# Dust1_MotherBoard_MCU.net
KiCad netlist of a schematic drawn in Altium Designer
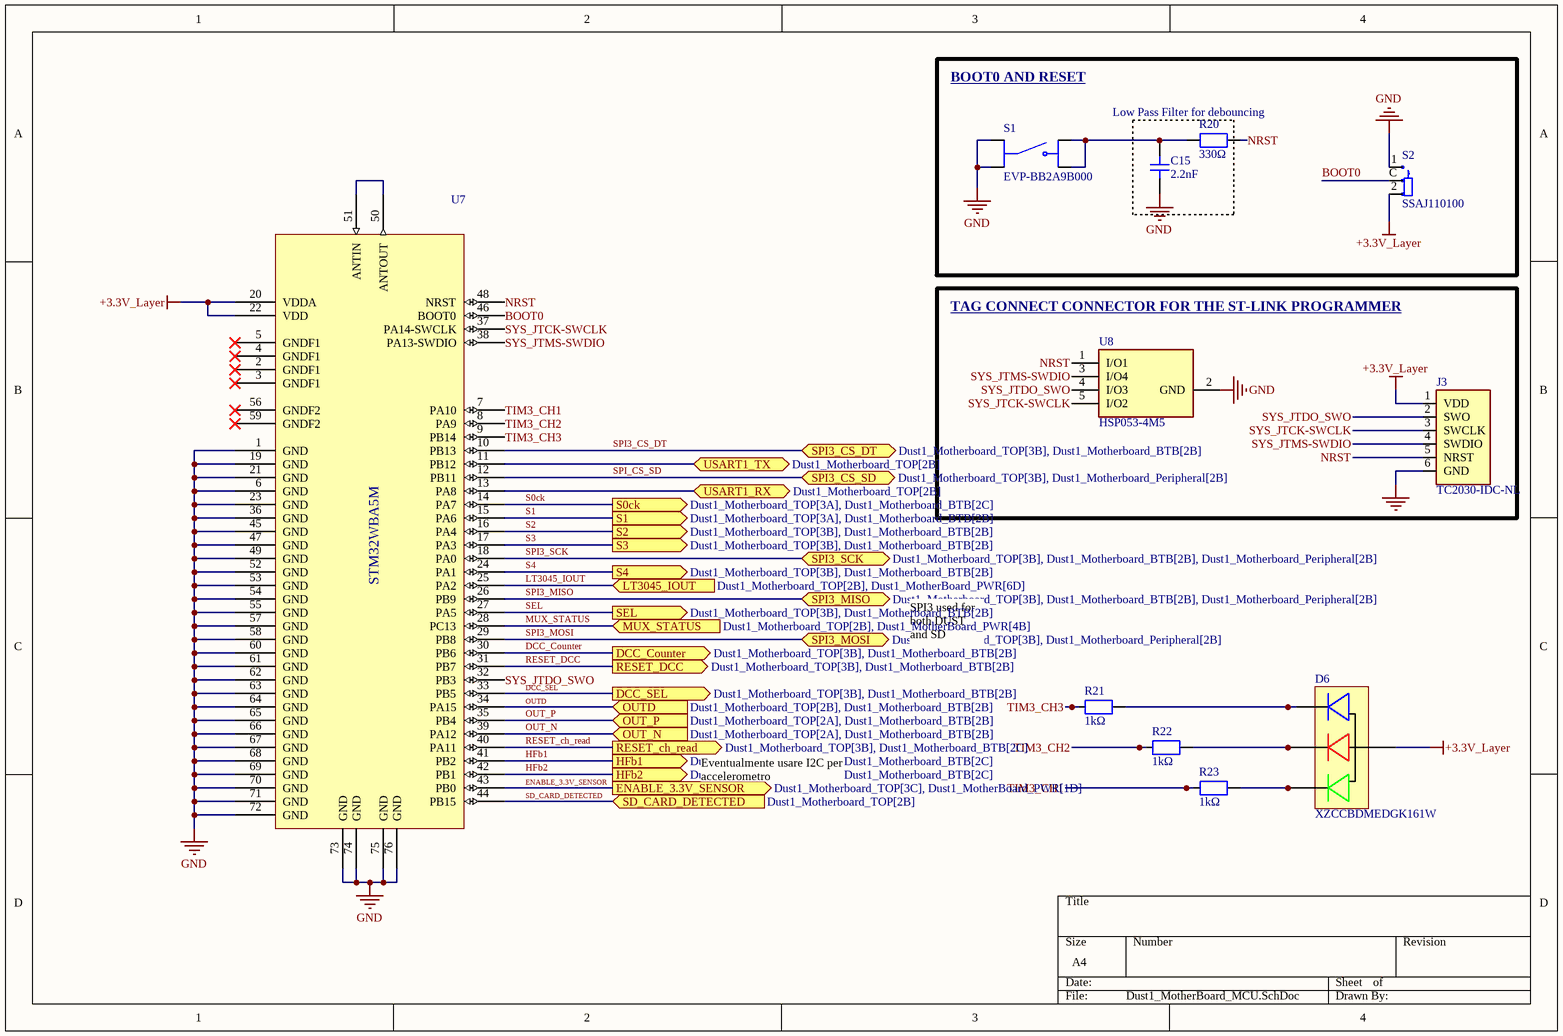
[diagram p0: Dust1_MotherBoard_MCU.SchDoc]

(export (version "E")
  (design (tool "Eeschema 10.0.6"))
  (components
    (comp (ref "C15")
      (value "2.2nF")
      (footprint "CAP_0402")
      (description "Generic 0402 Capacitor")
      (libsource (lib "I3N - LABSAMP") (part "CAP_0402"))
    )
    (comp (ref "D6")
      (value "XZCCBDMEDGK161W")
      (footprint "PCBComponent_1")
      (libsource (lib "I3N - LABSAMP") (part "XZCCBDMEDGK161W"))
    )
    (comp (ref "J3")
      (value "TC2030-IDC-NL")
      (footprint "TAG_TC2030-IDC-NL")
      (description "CABLE ADAPTER 6 POS")
      (libsource (lib "I3N - LABSAMP") (part "TC2030-IDC-NL"))
    )
    (comp (ref "R20")
      (value "330Ω")
      (footprint "RES_0402")
      (description "Resistor SMD 0402 Generic")
      (libsource (lib "I3N - LABSAMP") (part "RES_0402"))
    )
    (comp (ref "R21")
      (value "1kΩ")
      (footprint "RES_0402")
      (description "Resistor SMD 0402 Generic")
      (libsource (lib "I3N - LABSAMP") (part "RES_0402"))
    )
    (comp (ref "R22")
      (value "1kΩ")
      (footprint "RES_0402")
      (description "Resistor SMD 0402 Generic")
      (libsource (lib "I3N - LABSAMP") (part "RES_0402"))
    )
    (comp (ref "R23")
      (value "1kΩ")
      (footprint "RES_0402")
      (description "Resistor SMD 0402 Generic")
      (libsource (lib "I3N - LABSAMP") (part "RES_0402"))
    )
    (comp (ref "S1")
      (value "EVP-BB2A9B000")
      (footprint "SW_EVP-BB2A9B000")
      (description "Tactile Switch SPST-NO Top Actuated Surface Mount")
      (fields (field (name "MF") "Panasonic Electronic Components"))
      (libsource (lib "I3N - LABSAMP") (part "EVP-BB2A9B000"))
    )
    (comp (ref "S2")
      (value "SSAJ110100")
      (footprint "SW_SSAJ110100")
      (fields (field (name "MF") "ALPS"))
      (libsource (lib "I3N - LABSAMP") (part "SSAJ110100"))
    )
    (comp (ref "U7")
      (value "STM32WBA5MMG")
      (footprint "LGA76_stm32wba5mmg_C50P9X9_800X1250X137")
      (description "Bluetooth LE and IEEE 802.15.4 radio module")
      (libsource (lib "I3N - LABSAMP") (part "STM32WBA55MMG-Symbol-1"))
    )
    (comp (ref "U8")
      (value "HSP053-4M5")
      (footprint "HSP0534M5")
      (description "Clamp Ipp Tvs Diode Surface Mount 5-uQFN (1.3x0.8)")
      (fields (field (name "MOUSER PART NUMBER") "511-HSP053-4M5"))
      (libsource (lib "I3N - LABSAMP") (part "HSP053-4M5"))
    )
  )
  (nets
    (net (code "1") (name "+3.3V_Layer") (class "Default")
      (node (ref "D6") (pin "2") (pintype "passive"))
      (node (ref "J3") (pin "1") (pinfunction "VDD_1") (pintype "passive"))
      (node (ref "S2") (pin "2") (pinfunction "2_2") (pintype "passive"))
      (node (ref "U7") (pin "20") (pinfunction "VDDA_20") (pintype "power_in"))
      (node (ref "U7") (pin "22") (pinfunction "VDD_22") (pintype "power_in"))
    )
    (net (code "2") (name "/BOOT0") (class "Default")
      (node (ref "S2") (pin "C") (pinfunction "C_C") (pintype "passive"))
      (node (ref "U7") (pin "46") (pinfunction "BOOT0_46") (pintype "bidirectional"))
    )
    (net (code "3") (name "/DCC_Counter") (class "Default")
      (node (ref "U7") (pin "30") (pinfunction "PB6_30") (pintype "bidirectional"))
    )
    (net (code "4") (name "/DCC_SEL") (class "Default")
      (node (ref "U7") (pin "33") (pinfunction "PB5_33") (pintype "bidirectional"))
    )
    (net (code "5") (name "/ENABLE_3.3V_SENSOR") (class "Default")
      (node (ref "U7") (pin "43") (pinfunction "PB0_43") (pintype "bidirectional"))
    )
    (net (code "6") (name "/HFb1") (class "Default")
      (node (ref "U7") (pin "41") (pinfunction "PB2_41") (pintype "bidirectional"))
    )
    (net (code "7") (name "/HFb2") (class "Default")
      (node (ref "U7") (pin "42") (pinfunction "PB1_42") (pintype "bidirectional"))
    )
    (net (code "8") (name "/LT3045_IOUT") (class "Default")
      (node (ref "U7") (pin "25") (pinfunction "PA2_25") (pintype "bidirectional"))
    )
    (net (code "9") (name "/MUX_STATUS") (class "Default")
      (node (ref "U7") (pin "28") (pinfunction "PC13_28") (pintype "bidirectional"))
    )
    (net (code "10") (name "/NRST") (class "Default")
      (node (ref "J3") (pin "5") (pinfunction "NRST_5") (pintype "passive"))
      (node (ref "R20") (pin "2") (pintype "passive"))
      (node (ref "U7") (pin "48") (pinfunction "NRST_48") (pintype "bidirectional"))
      (node (ref "U8") (pin "1") (pinfunction "I/O1_1") (pintype "passive"))
    )
    (net (code "11") (name "/OUTD") (class "Default")
      (node (ref "U7") (pin "34") (pinfunction "PA15_34") (pintype "bidirectional"))
    )
    (net (code "12") (name "/OUT_N") (class "Default")
      (node (ref "U7") (pin "39") (pinfunction "PA12_39") (pintype "bidirectional"))
    )
    (net (code "13") (name "/OUT_P") (class "Default")
      (node (ref "U7") (pin "35") (pinfunction "PB4_35") (pintype "bidirectional"))
    )
    (net (code "14") (name "/RESET_DCC") (class "Default")
      (node (ref "U7") (pin "31") (pinfunction "PB7_31") (pintype "bidirectional"))
    )
    (net (code "15") (name "/RESET_ch_read") (class "Default")
      (node (ref "U7") (pin "40") (pinfunction "PA11_40") (pintype "bidirectional"))
    )
    (net (code "16") (name "/S0ck") (class "Default")
      (node (ref "U7") (pin "14") (pinfunction "PA7_14") (pintype "bidirectional"))
    )
    (net (code "17") (name "/S1") (class "Default")
      (node (ref "U7") (pin "15") (pinfunction "PA6_15") (pintype "bidirectional"))
    )
    (net (code "18") (name "/S2") (class "Default")
      (node (ref "U7") (pin "16") (pinfunction "PA4_16") (pintype "bidirectional"))
    )
    (net (code "19") (name "/S3") (class "Default")
      (node (ref "U7") (pin "17") (pinfunction "PA3_17") (pintype "bidirectional"))
    )
    (net (code "20") (name "/S4") (class "Default")
      (node (ref "U7") (pin "24") (pinfunction "PA1_24") (pintype "bidirectional"))
    )
    (net (code "21") (name "/SD_CARD_DETECTED") (class "Default")
      (node (ref "U7") (pin "44") (pinfunction "PB15_44") (pintype "bidirectional"))
    )
    (net (code "22") (name "/SEL") (class "Default")
      (node (ref "U7") (pin "27") (pinfunction "PA5_27") (pintype "bidirectional"))
    )
    (net (code "23") (name "/SPI3_CS_DT") (class "Default")
      (node (ref "U7") (pin "10") (pinfunction "PB13_10") (pintype "bidirectional"))
    )
    (net (code "24") (name "/SPI3_MISO") (class "Default")
      (node (ref "U7") (pin "26") (pinfunction "PB9_26") (pintype "bidirectional"))
    )
    (net (code "25") (name "/SPI3_MOSI") (class "Default")
      (node (ref "U7") (pin "29") (pinfunction "PB8_29") (pintype "bidirectional"))
    )
    (net (code "26") (name "/SPI3_SCK") (class "Default")
      (node (ref "U7") (pin "18") (pinfunction "PA0_18") (pintype "bidirectional"))
    )
    (net (code "27") (name "/SPI_CS_SD") (class "Default")
      (node (ref "U7") (pin "12") (pinfunction "PB11_12") (pintype "bidirectional"))
    )
    (net (code "28") (name "/SYS_JTCK-SWCLK") (class "Default")
      (node (ref "J3") (pin "3") (pinfunction "SWCLK_3") (pintype "passive"))
      (node (ref "U7") (pin "37") (pinfunction "PA14-SWCLK_37") (pintype "bidirectional"))
      (node (ref "U8") (pin "5") (pinfunction "I/O2_5") (pintype "passive"))
    )
    (net (code "29") (name "/SYS_JTDO_SWO") (class "Default")
      (node (ref "J3") (pin "2") (pinfunction "SWO_2") (pintype "passive"))
      (node (ref "U7") (pin "32") (pinfunction "PB3_32") (pintype "bidirectional"))
      (node (ref "U8") (pin "4") (pinfunction "I/O3_4") (pintype "passive"))
    )
    (net (code "30") (name "/SYS_JTMS-SWDIO") (class "Default")
      (node (ref "J3") (pin "4") (pinfunction "SWDIO_4") (pintype "passive"))
      (node (ref "U7") (pin "38") (pinfunction "PA13-SWDIO_38") (pintype "bidirectional"))
      (node (ref "U8") (pin "3") (pinfunction "I/O4_3") (pintype "passive"))
    )
    (net (code "31") (name "/TIM3_CH1") (class "Default")
      (node (ref "R23") (pin "1") (pintype "passive"))
      (node (ref "U7") (pin "7") (pinfunction "PA10_7") (pintype "bidirectional"))
    )
    (net (code "32") (name "/TIM3_CH2") (class "Default")
      (node (ref "R22") (pin "1") (pintype "passive"))
      (node (ref "U7") (pin "8") (pinfunction "PA9_8") (pintype "bidirectional"))
    )
    (net (code "33") (name "/TIM3_CH3") (class "Default")
      (node (ref "R21") (pin "1") (pintype "passive"))
      (node (ref "U7") (pin "9") (pinfunction "PB14_9") (pintype "bidirectional"))
    )
    (net (code "34") (name "/USART1_RX") (class "Default")
      (node (ref "U7") (pin "13") (pinfunction "PA8_13") (pintype "bidirectional"))
    )
    (net (code "35") (name "/USART1_TX") (class "Default")
      (node (ref "U7") (pin "11") (pinfunction "PB12_11") (pintype "bidirectional"))
    )
    (net (code "36") (name "GND") (class "Default")
      (node (ref "C15") (pin "1") (pintype "passive"))
      (node (ref "J3") (pin "6") (pinfunction "GND_6") (pintype "passive"))
      (node (ref "S1") (pin "A1") (pinfunction "A1_A1") (pintype "passive"))
      (node (ref "S1") (pin "A2") (pinfunction "A2_A2") (pintype "passive"))
      (node (ref "S2") (pin "1") (pinfunction "1_1") (pintype "passive"))
      (node (ref "U7") (pin "1") (pinfunction "GND_1") (pintype "power_in"))
      (node (ref "U7") (pin "19") (pinfunction "GND_19") (pintype "power_in"))
      (node (ref "U7") (pin "21") (pinfunction "GND_21") (pintype "power_in"))
      (node (ref "U7") (pin "23") (pinfunction "GND_23") (pintype "power_in"))
      (node (ref "U7") (pin "36") (pinfunction "GND_36") (pintype "power_in"))
      (node (ref "U7") (pin "45") (pinfunction "GND_45") (pintype "power_in"))
      (node (ref "U7") (pin "47") (pinfunction "GND_47") (pintype "power_in"))
      (node (ref "U7") (pin "49") (pinfunction "GND_49") (pintype "power_in"))
      (node (ref "U7") (pin "52") (pinfunction "GND_52") (pintype "power_in"))
      (node (ref "U7") (pin "53") (pinfunction "GND_53") (pintype "power_in"))
      (node (ref "U7") (pin "54") (pinfunction "GND_54") (pintype "power_in"))
      (node (ref "U7") (pin "55") (pinfunction "GND_55") (pintype "power_in"))
      (node (ref "U7") (pin "57") (pinfunction "GND_57") (pintype "power_in"))
      (node (ref "U7") (pin "58") (pinfunction "GND_58") (pintype "power_in"))
      (node (ref "U7") (pin "6") (pinfunction "GND_6") (pintype "power_in"))
      (node (ref "U7") (pin "60") (pinfunction "GND_60") (pintype "power_in"))
      (node (ref "U7") (pin "61") (pinfunction "GND_61") (pintype "power_in"))
      (node (ref "U7") (pin "62") (pinfunction "GND_62") (pintype "power_in"))
      (node (ref "U7") (pin "63") (pinfunction "GND_63") (pintype "power_in"))
      (node (ref "U7") (pin "64") (pinfunction "GND_64") (pintype "power_in"))
      (node (ref "U7") (pin "65") (pinfunction "GND_65") (pintype "power_in"))
      (node (ref "U7") (pin "66") (pinfunction "GND_66") (pintype "power_in"))
      (node (ref "U7") (pin "67") (pinfunction "GND_67") (pintype "power_in"))
      (node (ref "U7") (pin "68") (pinfunction "GND_68") (pintype "power_in"))
      (node (ref "U7") (pin "69") (pinfunction "GND_69") (pintype "power_in"))
      (node (ref "U7") (pin "70") (pinfunction "GND_70") (pintype "power_in"))
      (node (ref "U7") (pin "71") (pinfunction "GND_71") (pintype "power_in"))
      (node (ref "U7") (pin "72") (pinfunction "GND_72") (pintype "power_in"))
      (node (ref "U7") (pin "73") (pinfunction "GND_73") (pintype "power_in"))
      (node (ref "U7") (pin "74") (pinfunction "GND_74") (pintype "power_in"))
      (node (ref "U7") (pin "75") (pinfunction "GND_75") (pintype "power_in"))
      (node (ref "U7") (pin "76") (pinfunction "GND_76") (pintype "passive"))
      (node (ref "U8") (pin "2") (pinfunction "GND_2") (pintype "passive"))
    )
    (net (code "37") (name "Net-(C15-Pad2)") (class "Default")
      (node (ref "C15") (pin "2") (pintype "passive"))
      (node (ref "R20") (pin "1") (pintype "passive"))
      (node (ref "S1") (pin "B1") (pinfunction "B1_B1") (pintype "passive"))
      (node (ref "S1") (pin "B2") (pinfunction "B2_B2") (pintype "passive"))
    )
    (net (code "38") (name "Net-(D6-Pad1)") (class "Default")
      (node (ref "D6") (pin "1") (pintype "passive"))
      (node (ref "R21") (pin "2") (pintype "passive"))
    )
    (net (code "39") (name "Net-(D6-Pad3)") (class "Default")
      (node (ref "D6") (pin "3") (pintype "passive"))
      (node (ref "R22") (pin "2") (pintype "passive"))
    )
    (net (code "40") (name "Net-(D6-Pad4)") (class "Default")
      (node (ref "D6") (pin "4") (pintype "passive"))
      (node (ref "R23") (pin "2") (pintype "passive"))
    )
    (net (code "41") (name "Net-(U7-ANTIN)") (class "Default")
      (node (ref "U7") (pin "50") (pinfunction "ANTOUT_50") (pintype "output"))
      (node (ref "U7") (pin "51") (pinfunction "ANTIN_51") (pintype "input"))
    )
    (net (code "42") (name "unconnected-(U7-GNDF1-Pad2)") (class "Default")
      (node (ref "U7") (pin "2") (pinfunction "GNDF1_2") (pintype "power_in+no_connect"))
    )
    (net (code "43") (name "unconnected-(U7-GNDF1-Pad3)") (class "Default")
      (node (ref "U7") (pin "3") (pinfunction "GNDF1_3") (pintype "power_in+no_connect"))
    )
    (net (code "44") (name "unconnected-(U7-GNDF1-Pad4)") (class "Default")
      (node (ref "U7") (pin "4") (pinfunction "GNDF1_4") (pintype "power_in+no_connect"))
    )
    (net (code "45") (name "unconnected-(U7-GNDF1-Pad5)") (class "Default")
      (node (ref "U7") (pin "5") (pinfunction "GNDF1_5") (pintype "power_in+no_connect"))
    )
    (net (code "46") (name "unconnected-(U7-GNDF2-Pad56)") (class "Default")
      (node (ref "U7") (pin "56") (pinfunction "GNDF2_56") (pintype "power_in+no_connect"))
    )
    (net (code "47") (name "unconnected-(U7-GNDF2-Pad59)") (class "Default")
      (node (ref "U7") (pin "59") (pinfunction "GNDF2_59") (pintype "power_in+no_connect"))
    )
  )
)
